# v0_4_4.net
KiCad netlist of a schematic drawn in EAGLE
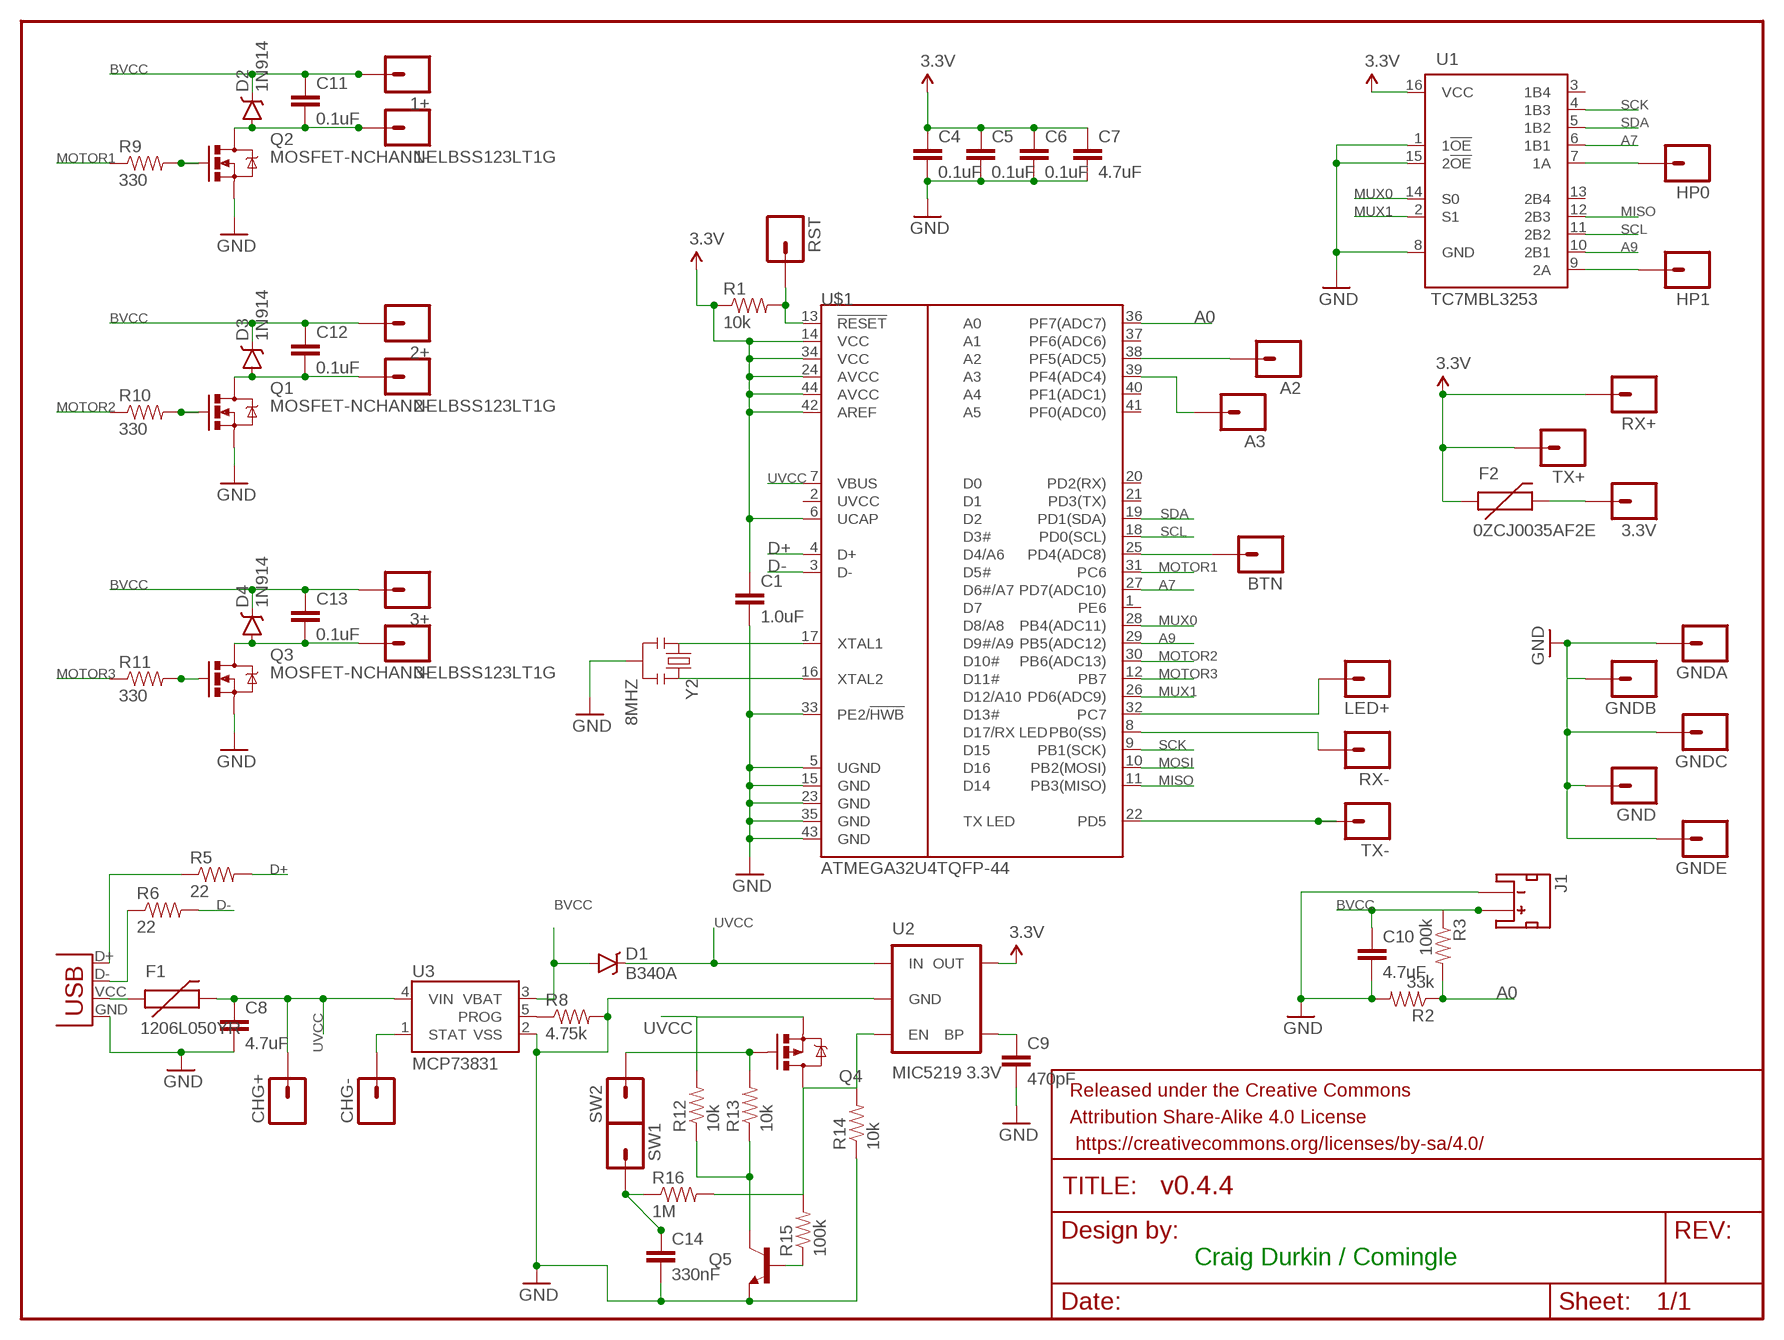
[diagram p0: schematic, sheet 1]

(export (version "E")
  (design (tool "Eeschema 10.0.6"))
  (components
    (comp (ref "1+")
      (value "M01PTH")
      (footprint "eagle-import:1X01")
      (libsource (lib "eagle-import") (part "M01PTH"))
    )
    (comp (ref "1-")
      (value "M01PTH")
      (footprint "eagle-import:1X01")
      (libsource (lib "eagle-import") (part "M01PTH"))
    )
    (comp (ref "2+")
      (value "M01PTH")
      (footprint "eagle-import:1X01")
      (libsource (lib "eagle-import") (part "M01PTH"))
    )
    (comp (ref "2-")
      (value "M01PTH")
      (footprint "eagle-import:1X01")
      (libsource (lib "eagle-import") (part "M01PTH"))
    )
    (comp (ref "3+")
      (value "M01PTH")
      (footprint "eagle-import:1X01")
      (libsource (lib "eagle-import") (part "M01PTH"))
    )
    (comp (ref "3-")
      (value "M01PTH")
      (footprint "eagle-import:1X01")
      (libsource (lib "eagle-import") (part "M01PTH"))
    )
    (comp (ref "3.3V")
      (value "M01PTH")
      (footprint "eagle-import:1X01")
      (libsource (lib "eagle-import") (part "M01PTH"))
    )
    (comp (ref "A2")
      (value "M01PTH")
      (footprint "eagle-import:1X01")
      (libsource (lib "eagle-import") (part "M01PTH"))
    )
    (comp (ref "A3")
      (value "M01PTH")
      (footprint "eagle-import:1X01")
      (libsource (lib "eagle-import") (part "M01PTH"))
    )
    (comp (ref "BTN")
      (value "M01PTH")
      (footprint "eagle-import:1X01")
      (libsource (lib "eagle-import") (part "M01PTH"))
    )
    (comp (ref "C1")
      (value "1.0uF")
      (footprint "eagle-import:0603-CAP")
      (libsource (lib "eagle-import") (part "CAP0603-CAP"))
    )
    (comp (ref "C4")
      (value "0.1uF")
      (footprint "eagle-import:0603-CAP")
      (libsource (lib "eagle-import") (part "SparkFun-Passives_CAP0603-CAP"))
    )
    (comp (ref "C5")
      (value "0.1uF")
      (footprint "eagle-import:0603-CAP")
      (libsource (lib "eagle-import") (part "SparkFun-Passives_CAP0603-CAP"))
    )
    (comp (ref "C6")
      (value "0.1uF")
      (footprint "eagle-import:0603-CAP")
      (libsource (lib "eagle-import") (part "SparkFun-Passives_CAP0603-CAP"))
    )
    (comp (ref "C7")
      (value "4.7uF")
      (footprint "eagle-import:0603-CAP")
      (libsource (lib "eagle-import") (part "SparkFun-Passives_CAP0603-CAP"))
    )
    (comp (ref "C8")
      (value "4.7uF")
      (footprint "eagle-import:1206")
      (libsource (lib "eagle-import") (part "SparkFun-Passives_CAP1206"))
    )
    (comp (ref "C9")
      (value "470pF")
      (footprint "eagle-import:0603-CAP")
      (libsource (lib "eagle-import") (part "CAP0603-CAP"))
    )
    (comp (ref "C10")
      (value "4.7uF")
      (footprint "eagle-import:1206")
      (libsource (lib "eagle-import") (part "SparkFun-Passives_CAP1206"))
    )
    (comp (ref "C11")
      (value "0.1uF")
      (footprint "eagle-import:0603-CAP")
      (libsource (lib "eagle-import") (part "CAP0603-CAP"))
    )
    (comp (ref "C12")
      (value "0.1uF")
      (footprint "eagle-import:0603-CAP")
      (libsource (lib "eagle-import") (part "CAP0603-CAP"))
    )
    (comp (ref "C13")
      (value "0.1uF")
      (footprint "eagle-import:0603-CAP")
      (libsource (lib "eagle-import") (part "CAP0603-CAP"))
    )
    (comp (ref "C14")
      (value "330nF")
      (footprint "eagle-import:0603-CAP")
      (libsource (lib "eagle-import") (part "CAP0603-CAP"))
    )
    (comp (ref "CHG+")
      (value "M01PTH")
      (footprint "eagle-import:1X01")
      (libsource (lib "eagle-import") (part "M01PTH"))
    )
    (comp (ref "CHG-")
      (value "M01PTH")
      (footprint "eagle-import:1X01")
      (libsource (lib "eagle-import") (part "M01PTH"))
    )
    (comp (ref "D1")
      (value "B340A")
      (footprint "eagle-import:SMA-DIODE")
      (libsource (lib "eagle-import") (part "DIODE-SCHOTTKY-B340A"))
    )
    (comp (ref "D2")
      (value "1N914")
      (footprint "eagle-import:SOD-323")
      (libsource (lib "eagle-import") (part "BAT20JFILM"))
    )
    (comp (ref "D3")
      (value "1N914")
      (footprint "eagle-import:SOD-323")
      (libsource (lib "eagle-import") (part "BAT20JFILM"))
    )
    (comp (ref "D4")
      (value "1N914")
      (footprint "eagle-import:SOD-323")
      (libsource (lib "eagle-import") (part "BAT20JFILM"))
    )
    (comp (ref "F1")
      (value "1206L050YR")
      (footprint "eagle-import:PTC-1206")
      (libsource (lib "eagle-import") (part "PTCSMD"))
    )
    (comp (ref "F2")
      (value "0ZCJ0035AF2E")
      (footprint "eagle-import:PTC-1206")
      (libsource (lib "eagle-import") (part "PTCSMD"))
    )
    (comp (ref "FRAME1")
      (value "FRAME-LETTER")
      (footprint "eagle-import:CREATIVE_COMMONS")
      (libsource (lib "eagle-import") (part "FRAME-LETTER"))
    )
    (comp (ref "GND")
      (value "M01PTH")
      (footprint "eagle-import:1X01")
      (libsource (lib "eagle-import") (part "M01PTH"))
    )
    (comp (ref "GNDA")
      (value "M01PTH")
      (footprint "eagle-import:1X01")
      (libsource (lib "eagle-import") (part "M01PTH"))
    )
    (comp (ref "GNDB")
      (value "M01PTH")
      (footprint "eagle-import:1X01")
      (libsource (lib "eagle-import") (part "M01PTH"))
    )
    (comp (ref "GNDC")
      (value "M01PTH")
      (footprint "eagle-import:1X01")
      (libsource (lib "eagle-import") (part "M01PTH"))
    )
    (comp (ref "GNDE")
      (value "M01PTH")
      (footprint "eagle-import:1X01")
      (libsource (lib "eagle-import") (part "M01PTH"))
    )
    (comp (ref "HP0")
      (value "M01PTH")
      (footprint "eagle-import:1X01")
      (libsource (lib "eagle-import") (part "M01PTH"))
    )
    (comp (ref "HP1")
      (value "M01PTH")
      (footprint "eagle-import:1X01")
      (libsource (lib "eagle-import") (part "M01PTH"))
    )
    (comp (ref "J1")
      (value "JST_2MM_MALE")
      (footprint "eagle-import:JST-2-SMD")
      (libsource (lib "eagle-import") (part "JST_2MM_MALE"))
    )
    (comp (ref "JP4")
      (value "USBMICROB-GCT-USB3075")
      (footprint "eagle-import:USB-MICROB-GCT-USB3075")
      (libsource (lib "eagle-import") (part "USBMICROB-GCT-USB3075"))
    )
    (comp (ref "LED+")
      (value "M01PTH")
      (footprint "eagle-import:1X01")
      (libsource (lib "eagle-import") (part "M01PTH"))
    )
    (comp (ref "Q1")
      (value "MOSFET-NCHANNELBSS123LT1G")
      (footprint "eagle-import:SOT23-3")
      (libsource (lib "eagle-import") (part "MOSFET-NCHANNELBSS123LT1G"))
    )
    (comp (ref "Q2")
      (value "MOSFET-NCHANNELBSS123LT1G")
      (footprint "eagle-import:SOT23-3")
      (libsource (lib "eagle-import") (part "MOSFET-NCHANNELBSS123LT1G"))
    )
    (comp (ref "Q3")
      (value "MOSFET-NCHANNELBSS123LT1G")
      (footprint "eagle-import:SOT23-3")
      (libsource (lib "eagle-import") (part "MOSFET-NCHANNELBSS123LT1G"))
    )
    (comp (ref "Q4")
      (value "NTS2101PT1G")
      (footprint "eagle-import:SOT323")
      (libsource (lib "eagle-import") (part "MOSFET-PCHANNELSOT323"))
    )
    (comp (ref "Q5")
      (value "MMBT2222A")
      (footprint "eagle-import:SOT23-3")
      (libsource (lib "eagle-import") (part "TRANSISTOR_NPNMMBT2222A"))
    )
    (comp (ref "R1")
      (value "10k")
      (footprint "eagle-import:0603-RES")
      (libsource (lib "eagle-import") (part "RESISTOR0603-RES"))
    )
    (comp (ref "R2")
      (value "33k")
      (footprint "eagle-import:0603-RES")
      (libsource (lib "eagle-import") (part "RESISTOR0603-RES"))
    )
    (comp (ref "R3")
      (value "100k")
      (footprint "eagle-import:0603-RES")
      (libsource (lib "eagle-import") (part "RESISTOR0603-RES"))
    )
    (comp (ref "R5")
      (value "22")
      (footprint "eagle-import:0603-RES")
      (libsource (lib "eagle-import") (part "RESISTOR0603-RES"))
    )
    (comp (ref "R6")
      (value "22")
      (footprint "eagle-import:0603-RES")
      (libsource (lib "eagle-import") (part "RESISTOR0603-RES"))
    )
    (comp (ref "R8")
      (value "4.75k")
      (footprint "eagle-import:0603-RES")
      (libsource (lib "eagle-import") (part "RESISTOR0603-RES"))
    )
    (comp (ref "R9")
      (value "330")
      (footprint "eagle-import:0603-RES")
      (libsource (lib "eagle-import") (part "RESISTOR0603-RES"))
    )
    (comp (ref "R10")
      (value "330")
      (footprint "eagle-import:0603-RES")
      (libsource (lib "eagle-import") (part "RESISTOR0603-RES"))
    )
    (comp (ref "R11")
      (value "330")
      (footprint "eagle-import:0603-RES")
      (libsource (lib "eagle-import") (part "RESISTOR0603-RES"))
    )
    (comp (ref "R12")
      (value "10k")
      (footprint "eagle-import:0603-RES")
      (libsource (lib "eagle-import") (part "RESISTOR0603-RES"))
    )
    (comp (ref "R13")
      (value "10k")
      (footprint "eagle-import:0603-RES")
      (libsource (lib "eagle-import") (part "RESISTOR0603-RES"))
    )
    (comp (ref "R14")
      (value "10k")
      (footprint "eagle-import:0603-RES")
      (libsource (lib "eagle-import") (part "RESISTOR0603-RES"))
    )
    (comp (ref "R15")
      (value "100k")
      (footprint "eagle-import:0603-RES")
      (libsource (lib "eagle-import") (part "RESISTOR0603-RES"))
    )
    (comp (ref "R16")
      (value "1M")
      (footprint "eagle-import:0603-RES")
      (libsource (lib "eagle-import") (part "RESISTOR0603-RES"))
    )
    (comp (ref "RST")
      (value "M01PTH")
      (footprint "eagle-import:1X01")
      (libsource (lib "eagle-import") (part "M01PTH"))
    )
    (comp (ref "RX+")
      (value "M01PTH")
      (footprint "eagle-import:1X01")
      (libsource (lib "eagle-import") (part "M01PTH"))
    )
    (comp (ref "RX-")
      (value "M01PTH")
      (footprint "eagle-import:1X01")
      (libsource (lib "eagle-import") (part "M01PTH"))
    )
    (comp (ref "SW1")
      (value "M01PTH")
      (footprint "eagle-import:1X01")
      (libsource (lib "eagle-import") (part "M01PTH"))
    )
    (comp (ref "SW2")
      (value "M01PTH")
      (footprint "eagle-import:1X01")
      (libsource (lib "eagle-import") (part "M01PTH"))
    )
    (comp (ref "TX+")
      (value "M01PTH")
      (footprint "eagle-import:1X01")
      (libsource (lib "eagle-import") (part "M01PTH"))
    )
    (comp (ref "TX-")
      (value "M01PTH")
      (footprint "eagle-import:1X01")
      (libsource (lib "eagle-import") (part "M01PTH"))
    )
    (comp (ref "U$1")
      (value "ATMEGA32U4TQFP-44")
      (footprint "eagle-import:TQFP44")
      (libsource (lib "eagle-import") (part "ATMEGA32U4TQFP-44"))
    )
    (comp (ref "U1")
      (value "TC7MBL3253")
      (footprint "eagle-import:SSOP16")
      (libsource (lib "eagle-import") (part "TC7MBL3253"))
    )
    (comp (ref "U2")
      (value "MIC5219 3.3V")
      (footprint "eagle-import:SOT23-5")
      (libsource (lib "eagle-import") (part "V_REG_MIC52193.3V"))
    )
    (comp (ref "U3")
      (value "MCP73831")
      (footprint "eagle-import:SOT23-5")
      (libsource (lib "eagle-import") (part "MCP73831"))
    )
    (comp (ref "Y2")
      (value "8MHZ")
      (footprint "eagle-import:RESONATOR-SMD")
      (libsource (lib "eagle-import") (part "RESONATOR8MHZ"))
    )
  )
  (nets
    (net (code "1") (name "/A0") (class "Default")
      (node (ref "R2") (pin "1") (pinfunction "1_1") (pintype "passive"))
      (node (ref "R3") (pin "2") (pinfunction "2_2") (pintype "passive"))
      (node (ref "U$1") (pin "36") (pinfunction "PF7(ADC7)_36") (pintype "bidirectional"))
    )
    (net (code "2") (name "/A7") (class "Default")
      (node (ref "U$1") (pin "27") (pinfunction "PD7(ADC10)_27") (pintype "bidirectional"))
      (node (ref "U1") (pin "6") (pinfunction "1B1_6") (pintype "bidirectional"))
    )
    (net (code "3") (name "/A9") (class "Default")
      (node (ref "U$1") (pin "29") (pinfunction "PB5(ADC12)_29") (pintype "bidirectional"))
      (node (ref "U1") (pin "10") (pinfunction "2B1_10") (pintype "bidirectional"))
    )
    (net (code "4") (name "/BVCC") (class "Default")
      (node (ref "1+") (pin "1") (pinfunction "1_1") (pintype "passive"))
      (node (ref "2+") (pin "1") (pinfunction "1_1") (pintype "passive"))
      (node (ref "3+") (pin "1") (pinfunction "1_1") (pintype "passive"))
      (node (ref "C10") (pin "1") (pinfunction "1_1") (pintype "passive"))
      (node (ref "C11") (pin "1") (pinfunction "1_1") (pintype "passive"))
      (node (ref "C12") (pin "1") (pinfunction "1_1") (pintype "passive"))
      (node (ref "C13") (pin "1") (pinfunction "1_1") (pintype "passive"))
      (node (ref "D1") (pin "A") (pinfunction "A_A") (pintype "passive"))
      (node (ref "D2") (pin "C") (pinfunction "C_C") (pintype "passive"))
      (node (ref "D3") (pin "C") (pinfunction "C_C") (pintype "passive"))
      (node (ref "D4") (pin "C") (pinfunction "C_C") (pintype "passive"))
      (node (ref "J1") (pin "2") (pinfunction "+_2") (pintype "bidirectional"))
      (node (ref "R3") (pin "1") (pinfunction "1_1") (pintype "passive"))
      (node (ref "U3") (pin "3") (pinfunction "VBAT_3") (pintype "power_in"))
    )
    (net (code "5") (name "/D+") (class "Default")
      (node (ref "R5") (pin "2") (pinfunction "2_2") (pintype "passive"))
      (node (ref "U$1") (pin "4") (pinfunction "D+_4") (pintype "bidirectional"))
    )
    (net (code "6") (name "/D-") (class "Default")
      (node (ref "R6") (pin "2") (pinfunction "2_2") (pintype "passive"))
      (node (ref "U$1") (pin "3") (pinfunction "D-_3") (pintype "bidirectional"))
    )
    (net (code "7") (name "/MISO") (class "Default")
      (node (ref "U$1") (pin "11") (pinfunction "PB3(MISO)_11") (pintype "bidirectional"))
      (node (ref "U1") (pin "12") (pinfunction "2B3_12") (pintype "bidirectional"))
    )
    (net (code "8") (name "/MOSI") (class "Default")
      (node (ref "U$1") (pin "10") (pinfunction "PB2(MOSI)_10") (pintype "bidirectional"))
    )
    (net (code "9") (name "/MOTOR1") (class "Default")
      (node (ref "R9") (pin "1") (pinfunction "1_1") (pintype "passive"))
      (node (ref "U$1") (pin "31") (pinfunction "PC6_31") (pintype "bidirectional"))
    )
    (net (code "10") (name "/MOTOR2") (class "Default")
      (node (ref "R10") (pin "1") (pinfunction "1_1") (pintype "passive"))
      (node (ref "U$1") (pin "30") (pinfunction "PB6(ADC13)_30") (pintype "bidirectional"))
    )
    (net (code "11") (name "/MOTOR3") (class "Default")
      (node (ref "R11") (pin "1") (pinfunction "1_1") (pintype "passive"))
      (node (ref "U$1") (pin "12") (pinfunction "PB7_12") (pintype "bidirectional"))
    )
    (net (code "12") (name "/MUX0") (class "Default")
      (node (ref "U$1") (pin "28") (pinfunction "PB4(ADC11)_28") (pintype "bidirectional"))
      (node (ref "U1") (pin "14") (pinfunction "S0_14") (pintype "bidirectional"))
    )
    (net (code "13") (name "/MUX1") (class "Default")
      (node (ref "U$1") (pin "26") (pinfunction "PD6(ADC9)_26") (pintype "bidirectional"))
      (node (ref "U1") (pin "2") (pinfunction "S1_2") (pintype "bidirectional"))
    )
    (net (code "14") (name "/SCK") (class "Default")
      (node (ref "U$1") (pin "9") (pinfunction "PB1(SCK)_9") (pintype "bidirectional"))
      (node (ref "U1") (pin "4") (pinfunction "1B3_4") (pintype "bidirectional"))
    )
    (net (code "15") (name "/SCL") (class "Default")
      (node (ref "U$1") (pin "18") (pinfunction "PD0(SCL)_18") (pintype "bidirectional"))
      (node (ref "U1") (pin "11") (pinfunction "2B2_11") (pintype "bidirectional"))
    )
    (net (code "16") (name "/SDA") (class "Default")
      (node (ref "U$1") (pin "19") (pinfunction "PD1(SDA)_19") (pintype "bidirectional"))
      (node (ref "U1") (pin "5") (pinfunction "1B2_5") (pintype "bidirectional"))
    )
    (net (code "17") (name "/UVCC") (class "Default")
      (node (ref "C8") (pin "1") (pinfunction "1_1") (pintype "passive"))
      (node (ref "CHG+") (pin "1") (pinfunction "1_1") (pintype "passive"))
      (node (ref "D1") (pin "C") (pinfunction "C_C") (pintype "passive"))
      (node (ref "F1") (pin "2") (pinfunction "2_2") (pintype "bidirectional"))
      (node (ref "Q4") (pin "2") (pinfunction "S_2") (pintype "passive"))
      (node (ref "R12") (pin "2") (pinfunction "2_2") (pintype "passive"))
      (node (ref "U$1") (pin "7") (pinfunction "VBUS_7") (pintype "bidirectional"))
      (node (ref "U2") (pin "1") (pinfunction "IN_1") (pintype "input"))
      (node (ref "U3") (pin "4") (pinfunction "VIN_4") (pintype "power_in"))
    )
    (net (code "18") (name "3.3V") (class "Default")
      (node (ref "C1") (pin "1") (pinfunction "1_1") (pintype "passive"))
      (node (ref "C4") (pin "1") (pinfunction "1_1") (pintype "passive"))
      (node (ref "C5") (pin "1") (pinfunction "1_1") (pintype "passive"))
      (node (ref "C6") (pin "1") (pinfunction "1_1") (pintype "passive"))
      (node (ref "C7") (pin "1") (pinfunction "1_1") (pintype "passive"))
      (node (ref "F2") (pin "1") (pinfunction "1_1") (pintype "bidirectional"))
      (node (ref "R1") (pin "1") (pinfunction "1_1") (pintype "passive"))
      (node (ref "RX+") (pin "1") (pinfunction "1_1") (pintype "passive"))
      (node (ref "TX+") (pin "1") (pinfunction "1_1") (pintype "passive"))
      (node (ref "U$1") (pin "14") (pinfunction "VCC_14") (pintype "bidirectional"))
      (node (ref "U$1") (pin "24") (pinfunction "AVCC_24") (pintype "bidirectional"))
      (node (ref "U$1") (pin "34") (pinfunction "VCC_34") (pintype "bidirectional"))
      (node (ref "U$1") (pin "42") (pinfunction "AREF_42") (pintype "bidirectional"))
      (node (ref "U$1") (pin "44") (pinfunction "AVCC_44") (pintype "bidirectional"))
      (node (ref "U$1") (pin "6") (pinfunction "UCAP_6") (pintype "bidirectional"))
      (node (ref "U1") (pin "16") (pinfunction "VCC_16") (pintype "power_in"))
      (node (ref "U2") (pin "5") (pinfunction "OUT_5") (pintype "passive"))
    )
    (net (code "19") (name "GND") (class "Default")
      (node (ref "C1") (pin "2") (pinfunction "2_2") (pintype "passive"))
      (node (ref "C10") (pin "2") (pinfunction "2_2") (pintype "passive"))
      (node (ref "C14") (pin "2") (pinfunction "2_2") (pintype "passive"))
      (node (ref "C4") (pin "2") (pinfunction "2_2") (pintype "passive"))
      (node (ref "C5") (pin "2") (pinfunction "2_2") (pintype "passive"))
      (node (ref "C6") (pin "2") (pinfunction "2_2") (pintype "passive"))
      (node (ref "C7") (pin "2") (pinfunction "2_2") (pintype "passive"))
      (node (ref "C8") (pin "2") (pinfunction "2_2") (pintype "passive"))
      (node (ref "C9") (pin "2") (pinfunction "2_2") (pintype "passive"))
      (node (ref "GND") (pin "1") (pinfunction "1_1") (pintype "passive"))
      (node (ref "GNDA") (pin "1") (pinfunction "1_1") (pintype "passive"))
      (node (ref "GNDB") (pin "1") (pinfunction "1_1") (pintype "passive"))
      (node (ref "GNDC") (pin "1") (pinfunction "1_1") (pintype "passive"))
      (node (ref "GNDE") (pin "1") (pinfunction "1_1") (pintype "passive"))
      (node (ref "J1") (pin "1") (pinfunction "-_1") (pintype "bidirectional"))
      (node (ref "JP4") (pin "GND") (pinfunction "GND_GND") (pintype "bidirectional"))
      (node (ref "Q1") (pin "2") (pinfunction "S_2") (pintype "passive"))
      (node (ref "Q2") (pin "2") (pinfunction "S_2") (pintype "passive"))
      (node (ref "Q3") (pin "2") (pinfunction "S_2") (pintype "passive"))
      (node (ref "Q5") (pin "2") (pinfunction "E_2") (pintype "passive"))
      (node (ref "R14") (pin "1") (pinfunction "1_1") (pintype "passive"))
      (node (ref "R2") (pin "2") (pinfunction "2_2") (pintype "passive"))
      (node (ref "R8") (pin "2") (pinfunction "2_2") (pintype "passive"))
      (node (ref "U$1") (pin "15") (pinfunction "GND_15") (pintype "bidirectional"))
      (node (ref "U$1") (pin "23") (pinfunction "GND_23") (pintype "bidirectional"))
      (node (ref "U$1") (pin "33") (pinfunction "PE2/~{HWB}_33") (pintype "bidirectional"))
      (node (ref "U$1") (pin "35") (pinfunction "GND_35") (pintype "bidirectional"))
      (node (ref "U$1") (pin "43") (pinfunction "GND_43") (pintype "bidirectional"))
      (node (ref "U$1") (pin "5") (pinfunction "UGND_5") (pintype "bidirectional"))
      (node (ref "U1") (pin "1") (pinfunction "1~{OE}_1") (pintype "input"))
      (node (ref "U1") (pin "15") (pinfunction "2~{OE}_15") (pintype "input"))
      (node (ref "U1") (pin "8") (pinfunction "GND_8") (pintype "power_in"))
      (node (ref "U2") (pin "2") (pinfunction "GND_2") (pintype "input"))
      (node (ref "U3") (pin "2") (pinfunction "VSS_2") (pintype "power_in"))
      (node (ref "Y2") (pin "2") (pinfunction "2_2") (pintype "passive"))
    )
    (net (code "20") (name "Net-(3.3V-Pad1)") (class "Default")
      (node (ref "3.3V") (pin "1") (pinfunction "1_1") (pintype "passive"))
      (node (ref "F2") (pin "2") (pinfunction "2_2") (pintype "bidirectional"))
    )
    (net (code "21") (name "Net-(C14-Pad1)") (class "Default")
      (node (ref "C14") (pin "1") (pinfunction "1_1") (pintype "passive"))
      (node (ref "R16") (pin "1") (pinfunction "1_1") (pintype "passive"))
      (node (ref "SW1") (pin "1") (pinfunction "1_1") (pintype "passive"))
    )
    (net (code "22") (name "Net-(JP4-PadD+)") (class "Default")
      (node (ref "JP4") (pin "D+") (pinfunction "D+_D+") (pintype "bidirectional"))
      (node (ref "R5") (pin "1") (pinfunction "1_1") (pintype "passive"))
    )
    (net (code "23") (name "Net-(JP4-PadD-)") (class "Default")
      (node (ref "JP4") (pin "D-") (pinfunction "D-_D-") (pintype "bidirectional"))
      (node (ref "R6") (pin "1") (pinfunction "1_1") (pintype "passive"))
    )
    (net (code "24") (name "Net-(JP4-VBUS)") (class "Default")
      (node (ref "F1") (pin "1") (pinfunction "1_1") (pintype "bidirectional"))
      (node (ref "JP4") (pin "VCC") (pinfunction "VBUS_VCC") (pintype "bidirectional"))
    )
    (net (code "25") (name "Net-(Q1-D)") (class "Default")
      (node (ref "2-") (pin "1") (pinfunction "1_1") (pintype "passive"))
      (node (ref "C12") (pin "2") (pinfunction "2_2") (pintype "passive"))
      (node (ref "D3") (pin "A") (pinfunction "A_A") (pintype "passive"))
      (node (ref "Q1") (pin "3") (pinfunction "D_3") (pintype "passive"))
    )
    (net (code "26") (name "Net-(Q1-G)") (class "Default")
      (node (ref "Q1") (pin "1") (pinfunction "G_1") (pintype "passive"))
      (node (ref "R10") (pin "2") (pinfunction "2_2") (pintype "passive"))
    )
    (net (code "27") (name "Net-(Q2-D)") (class "Default")
      (node (ref "1-") (pin "1") (pinfunction "1_1") (pintype "passive"))
      (node (ref "C11") (pin "2") (pinfunction "2_2") (pintype "passive"))
      (node (ref "D2") (pin "A") (pinfunction "A_A") (pintype "passive"))
      (node (ref "Q2") (pin "3") (pinfunction "D_3") (pintype "passive"))
    )
    (net (code "28") (name "Net-(Q2-G)") (class "Default")
      (node (ref "Q2") (pin "1") (pinfunction "G_1") (pintype "passive"))
      (node (ref "R9") (pin "2") (pinfunction "2_2") (pintype "passive"))
    )
    (net (code "29") (name "Net-(Q3-D)") (class "Default")
      (node (ref "3-") (pin "1") (pinfunction "1_1") (pintype "passive"))
      (node (ref "C13") (pin "2") (pinfunction "2_2") (pintype "passive"))
      (node (ref "D4") (pin "A") (pinfunction "A_A") (pintype "passive"))
      (node (ref "Q3") (pin "3") (pinfunction "D_3") (pintype "passive"))
    )
    (net (code "30") (name "Net-(Q3-G)") (class "Default")
      (node (ref "Q3") (pin "1") (pinfunction "G_1") (pintype "passive"))
      (node (ref "R11") (pin "2") (pinfunction "2_2") (pintype "passive"))
    )
    (net (code "31") (name "Net-(Q4-D)") (class "Default")
      (node (ref "Q4") (pin "3") (pinfunction "D_3") (pintype "passive"))
      (node (ref "R14") (pin "2") (pinfunction "2_2") (pintype "passive"))
      (node (ref "R15") (pin "2") (pinfunction "2_2") (pintype "passive"))
      (node (ref "R16") (pin "2") (pinfunction "2_2") (pintype "passive"))
      (node (ref "U2") (pin "3") (pinfunction "EN_3") (pintype "input"))
    )
    (net (code "32") (name "Net-(Q4-G)") (class "Default")
      (node (ref "Q4") (pin "1") (pinfunction "G_1") (pintype "passive"))
      (node (ref "R13") (pin "2") (pinfunction "2_2") (pintype "passive"))
      (node (ref "SW2") (pin "1") (pinfunction "1_1") (pintype "passive"))
    )
    (net (code "33") (name "Net-(Q5-B)") (class "Default")
      (node (ref "Q5") (pin "1") (pinfunction "B_1") (pintype "passive"))
      (node (ref "R15") (pin "1") (pinfunction "1_1") (pintype "passive"))
    )
    (net (code "34") (name "Net-(Q5-C)") (class "Default")
      (node (ref "Q5") (pin "3") (pinfunction "C_3") (pintype "passive"))
      (node (ref "R12") (pin "1") (pinfunction "1_1") (pintype "passive"))
      (node (ref "R13") (pin "1") (pinfunction "1_1") (pintype "passive"))
    )
    (net (code "35") (name "Net-(U$1-PB0(SS))") (class "Default")
      (node (ref "RX-") (pin "1") (pinfunction "1_1") (pintype "passive"))
      (node (ref "U$1") (pin "8") (pinfunction "PB0(SS)_8") (pintype "bidirectional"))
    )
    (net (code "36") (name "Net-(U$1-PC7)") (class "Default")
      (node (ref "LED+") (pin "1") (pinfunction "1_1") (pintype "passive"))
      (node (ref "U$1") (pin "32") (pinfunction "PC7_32") (pintype "bidirectional"))
    )
    (net (code "37") (name "Net-(U$1-PD4(ADC8))") (class "Default")
      (node (ref "BTN") (pin "1") (pinfunction "1_1") (pintype "passive"))
      (node (ref "U$1") (pin "25") (pinfunction "PD4(ADC8)_25") (pintype "bidirectional"))
    )
    (net (code "38") (name "Net-(U$1-PD5)") (class "Default")
      (node (ref "TX-") (pin "1") (pinfunction "1_1") (pintype "passive"))
      (node (ref "U$1") (pin "22") (pinfunction "PD5_22") (pintype "bidirectional"))
    )
    (net (code "39") (name "Net-(U$1-PF4(ADC4))") (class "Default")
      (node (ref "A3") (pin "1") (pinfunction "1_1") (pintype "passive"))
      (node (ref "U$1") (pin "39") (pinfunction "PF4(ADC4)_39") (pintype "bidirectional"))
    )
    (net (code "40") (name "Net-(U$1-PF5(ADC5))") (class "Default")
      (node (ref "A2") (pin "1") (pinfunction "1_1") (pintype "passive"))
      (node (ref "U$1") (pin "38") (pinfunction "PF5(ADC5)_38") (pintype "bidirectional"))
    )
    (net (code "41") (name "Net-(U$1-XTAL1)") (class "Default")
      (node (ref "U$1") (pin "17") (pinfunction "XTAL1_17") (pintype "bidirectional"))
      (node (ref "Y2") (pin "1") (pinfunction "1_1") (pintype "passive"))
    )
    (net (code "42") (name "Net-(U$1-XTAL2)") (class "Default")
      (node (ref "U$1") (pin "16") (pinfunction "XTAL2_16") (pintype "bidirectional"))
      (node (ref "Y2") (pin "3") (pinfunction "3_3") (pintype "passive"))
    )
    (net (code "43") (name "Net-(U$1-~{RESET})") (class "Default")
      (node (ref "R1") (pin "2") (pinfunction "2_2") (pintype "passive"))
      (node (ref "RST") (pin "1") (pinfunction "1_1") (pintype "passive"))
      (node (ref "U$1") (pin "13") (pinfunction "~{RESET}_13") (pintype "bidirectional"))
    )
    (net (code "44") (name "Net-(U1-1A)") (class "Default")
      (node (ref "HP0") (pin "1") (pinfunction "1_1") (pintype "passive"))
      (node (ref "U1") (pin "7") (pinfunction "1A_7") (pintype "bidirectional"))
    )
    (net (code "45") (name "Net-(U1-2A)") (class "Default")
      (node (ref "HP1") (pin "1") (pinfunction "1_1") (pintype "passive"))
      (node (ref "U1") (pin "9") (pinfunction "2A_9") (pintype "bidirectional"))
    )
    (net (code "46") (name "Net-(U2-BP)") (class "Default")
      (node (ref "C9") (pin "1") (pinfunction "1_1") (pintype "passive"))
      (node (ref "U2") (pin "4") (pinfunction "BP_4") (pintype "input"))
    )
    (net (code "47") (name "Net-(U3-PROG)") (class "Default")
      (node (ref "R8") (pin "1") (pinfunction "1_1") (pintype "passive"))
      (node (ref "U3") (pin "5") (pinfunction "PROG_5") (pintype "bidirectional"))
    )
    (net (code "48") (name "Net-(U3-STAT)") (class "Default")
      (node (ref "CHG-") (pin "1") (pinfunction "1_1") (pintype "passive"))
      (node (ref "U3") (pin "1") (pinfunction "STAT_1") (pintype "output"))
    )
    (net (code "49") (name "unconnected-(J1-PAD1-PadNC1)") (class "Default")
      (node (ref "J1") (pin "NC1") (pinfunction "PAD1_NC1") (pintype "bidirectional"))
    )
    (net (code "50") (name "unconnected-(J1-PAD2-PadNC2)") (class "Default")
      (node (ref "J1") (pin "NC2") (pinfunction "PAD2_NC2") (pintype "bidirectional"))
    )
    (net (code "51") (name "unconnected-(U$1-PD2(RX)-Pad20)") (class "Default")
      (node (ref "U$1") (pin "20") (pinfunction "PD2(RX)_20") (pintype "bidirectional"))
    )
    (net (code "52") (name "unconnected-(U$1-PD3(TX)-Pad21)") (class "Default")
      (node (ref "U$1") (pin "21") (pinfunction "PD3(TX)_21") (pintype "bidirectional"))
    )
    (net (code "53") (name "unconnected-(U$1-PE6-Pad1)") (class "Default")
      (node (ref "U$1") (pin "1") (pinfunction "PE6_1") (pintype "bidirectional"))
    )
    (net (code "54") (name "unconnected-(U$1-PF0(ADC0)-Pad41)") (class "Default")
      (node (ref "U$1") (pin "41") (pinfunction "PF0(ADC0)_41") (pintype "bidirectional"))
    )
    (net (code "55") (name "unconnected-(U$1-PF1(ADC1)-Pad40)") (class "Default")
      (node (ref "U$1") (pin "40") (pinfunction "PF1(ADC1)_40") (pintype "bidirectional"))
    )
    (net (code "56") (name "unconnected-(U$1-PF6(ADC6)-Pad37)") (class "Default")
      (node (ref "U$1") (pin "37") (pinfunction "PF6(ADC6)_37") (pintype "bidirectional"))
    )
    (net (code "57") (name "unconnected-(U$1-UVCC-Pad2)") (class "Default")
      (node (ref "U$1") (pin "2") (pinfunction "UVCC_2") (pintype "bidirectional"))
    )
    (net (code "58") (name "unconnected-(U1-1B4-Pad3)") (class "Default")
      (node (ref "U1") (pin "3") (pinfunction "1B4_3") (pintype "bidirectional"))
    )
    (net (code "59") (name "unconnected-(U1-2B4-Pad13)") (class "Default")
      (node (ref "U1") (pin "13") (pinfunction "2B4_13") (pintype "bidirectional"))
    )
  )
)
